# QCopterRC_EXTERN_Sch.net
KiCad netlist of a schematic drawn in Altium Designer
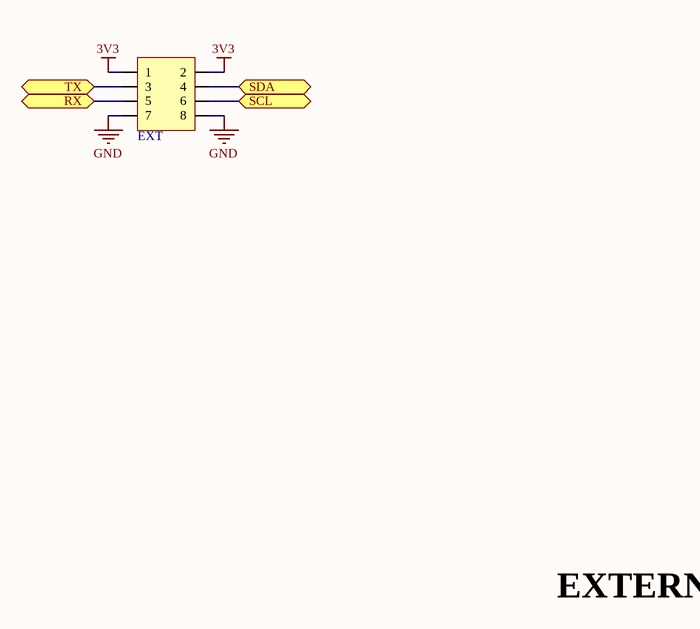
[diagram p0: QCopterRC_EXTERN_Sch.SchDoc]

(export (version "E")
  (design (tool "Eeschema 10.0.6"))
  (components
    (comp (ref "EXT")
      (value "HDR2X4_90_2.54")
      (footprint "PCB_Connector:HDR2X4_90_2.54")
      (description "Header")
      (libsource (lib "SCH_Connector") (part "HDR2X4_90_2.54"))
    )
  )
  (nets
    (net (code "2") (name "/RX") (class "Default")
      (node (ref "EXT") (pin "5") (pinfunction "5_5") (pintype "passive"))
    )
    (net (code "3") (name "/SCL") (class "Default")
      (node (ref "EXT") (pin "6") (pinfunction "6_6") (pintype "passive"))
    )
    (net (code "4") (name "/SDA") (class "Default")
      (node (ref "EXT") (pin "4") (pinfunction "4_4") (pintype "passive"))
    )
    (net (code "5") (name "/TX") (class "Default")
      (node (ref "EXT") (pin "3") (pinfunction "3_3") (pintype "passive"))
    )
    (net (code "6") (name "3V3") (class "Default")
      (node (ref "EXT") (pin "1") (pinfunction "1_1") (pintype "passive"))
      (node (ref "EXT") (pin "2") (pinfunction "2_2") (pintype "passive"))
    )
    (net (code "7") (name "GND") (class "Default")
      (node (ref "EXT") (pin "7") (pinfunction "7_7") (pintype "passive"))
      (node (ref "EXT") (pin "8") (pinfunction "8_8") (pintype "passive"))
    )
  )
)
